# design.net
KiCad netlist of a schematic drawn in Altium Designer
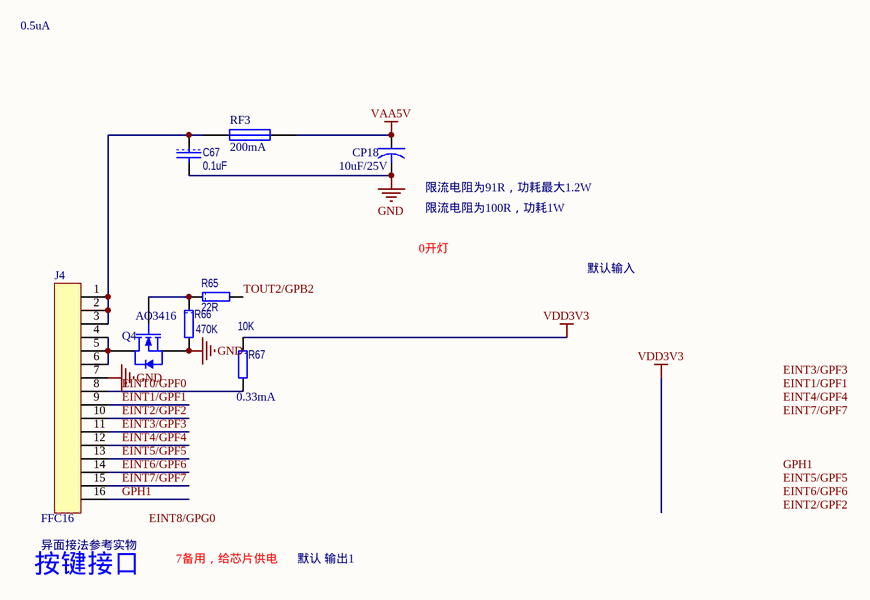
[diagram p0: 按键接口.SchDoc]

(export (version "E")
  (design (tool "Eeschema 10.0.6"))
  (components
    (comp (ref "C67")
      (value "0.1uF")
      (footprint "1608[0603]")
      (description "Capacitor")
      (fields (field (name "MANUFACTURER") "TDK"))
      (libsource (lib "*") (part "CAP"))
    )
    (comp (ref "CP18")
      (value "10uF/25V")
      (footprint "6032[2312]CC")
      (description "Tantalum Capacitor")
      (libsource (lib "*") (part "CAPACITOR"))
    )
    (comp (ref "J4")
      (value "FFC16")
      (footprint "FFC/SM0.5-2H16")
      (description "CON")
      (libsource (lib "*") (part "16PIN"))
    )
    (comp (ref "Q4")
      (value "AO3416")
      (footprint "SOT23_N")
      (description "NMOS")
      (fields (field (name "PUBLISHER") "Altium Limited"))
      (libsource (lib "Philips Discrete MOSFET - Low Power") (part "2N7002"))
    )
    (comp (ref "R65")
      (value "22R")
      (footprint "1608[0603]R")
      (description "RES")
      (fields (field (name "MANUFACTURER") "vishay"))
      (libsource (lib "*") (part "RES"))
    )
    (comp (ref "R66")
      (value "470K")
      (footprint "1608[0603]R")
      (description "RES")
      (fields (field (name "MANUFACTURER") "vishay"))
      (libsource (lib "*") (part "RES"))
    )
    (comp (ref "R67")
      (value "10K")
      (footprint "1608[0603]R")
      (description "RES")
      (fields (field (name "MANUFACTURER") "vishay"))
      (libsource (lib "*") (part "RES"))
    )
    (comp (ref "RF3")
      (value "200mA")
      (footprint "2012[0805]F")
      (description "FUSE")
      (fields (field (name "Comment") "NanoSMDC020F"))
      (libsource (lib "*") (part "FUSE1"))
    )
  )
  (nets
    (net (code "1") (name "/EINT0{slash}GPF0") (class "Default")
      (node (ref "J4") (pin "8") (pinfunction "8_8") (pintype "passive"))
      (node (ref "R67") (pin "2") (pinfunction "2_2") (pintype "passive"))
    )
    (net (code "2") (name "/EINT1{slash}GPF1") (class "Default")
      (node (ref "J4") (pin "9") (pinfunction "9_9") (pintype "passive"))
    )
    (net (code "3") (name "/EINT2{slash}GPF2") (class "Default")
      (node (ref "J4") (pin "10") (pinfunction "10_10") (pintype "passive"))
    )
    (net (code "4") (name "/EINT3{slash}GPF3") (class "Default")
      (node (ref "J4") (pin "11") (pinfunction "11_11") (pintype "passive"))
    )
    (net (code "5") (name "/EINT4{slash}GPF4") (class "Default")
      (node (ref "J4") (pin "12") (pinfunction "12_12") (pintype "passive"))
    )
    (net (code "6") (name "/EINT5{slash}GPF5") (class "Default")
      (node (ref "J4") (pin "13") (pinfunction "13_13") (pintype "passive"))
    )
    (net (code "7") (name "/EINT6{slash}GPF6") (class "Default")
      (node (ref "J4") (pin "14") (pinfunction "14_14") (pintype "passive"))
    )
    (net (code "8") (name "/EINT7{slash}GPF7") (class "Default")
      (node (ref "J4") (pin "15") (pinfunction "15_15") (pintype "passive"))
    )
    (net (code "10") (name "/GPH1") (class "Default")
      (node (ref "J4") (pin "16") (pinfunction "16_16") (pintype "passive"))
    )
    (net (code "11") (name "/TOUT2{slash}GPB2") (class "Default")
      (node (ref "R65") (pin "2") (pinfunction "2_2") (pintype "passive"))
    )
    (net (code "12") (name "GND") (class "Default")
      (node (ref "C67") (pin "2") (pinfunction "2_2") (pintype "passive"))
      (node (ref "CP18") (pin "2") (pinfunction "2_2") (pintype "passive"))
      (node (ref "J4") (pin "7") (pinfunction "7_7") (pintype "passive"))
      (node (ref "Q4") (pin "2") (pinfunction "S_2") (pintype "passive"))
      (node (ref "R66") (pin "2") (pinfunction "2_2") (pintype "passive"))
    )
    (net (code "13") (name "Net-(C67-Pad1)") (class "Default")
      (node (ref "C67") (pin "1") (pinfunction "1_1") (pintype "passive"))
      (node (ref "J4") (pin "1") (pinfunction "1_1") (pintype "passive"))
      (node (ref "J4") (pin "2") (pinfunction "2_2") (pintype "passive"))
      (node (ref "J4") (pin "3") (pinfunction "3_3") (pintype "passive"))
      (node (ref "RF3") (pin "1") (pinfunction "1_1") (pintype "passive"))
    )
    (net (code "14") (name "Net-(Q4-D)") (class "Default")
      (node (ref "J4") (pin "4") (pinfunction "4_4") (pintype "passive"))
      (node (ref "J4") (pin "5") (pinfunction "5_5") (pintype "passive"))
      (node (ref "J4") (pin "6") (pinfunction "6_6") (pintype "passive"))
      (node (ref "Q4") (pin "3") (pinfunction "D_3") (pintype "passive"))
    )
    (net (code "15") (name "Net-(Q4-G)") (class "Default")
      (node (ref "Q4") (pin "1") (pinfunction "G_1") (pintype "passive"))
      (node (ref "R65") (pin "1") (pinfunction "1_1") (pintype "passive"))
      (node (ref "R66") (pin "1") (pinfunction "1_1") (pintype "passive"))
    )
    (net (code "16") (name "VAA5V") (class "Default")
      (node (ref "CP18") (pin "1") (pinfunction "1_1") (pintype "passive"))
      (node (ref "RF3") (pin "2") (pinfunction "2_2") (pintype "passive"))
    )
    (net (code "17") (name "VDD3V3") (class "Default")
      (node (ref "R67") (pin "1") (pinfunction "1_1") (pintype "passive"))
    )
  )
)
